# microwaveBoardAntenna.net
KiCad netlist of a schematic drawn in Altium Designer
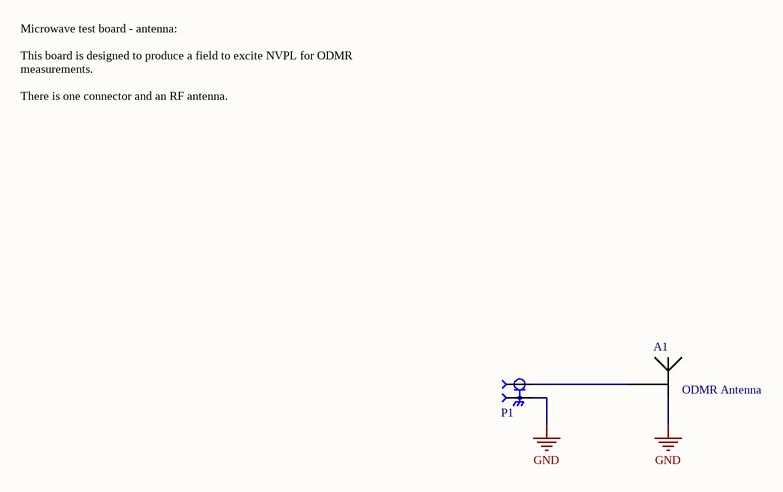
[diagram p0: microwaveBoardAntenna.SchDoc]

(export (version "E")
  (design (tool "Eeschema 10.0.6"))
  (components
    (comp (ref "A1")
      (value "ODMR Antenna")
      (footprint "ODMR_Antenna")
      (description "antenna")
      (libsource (lib "SorensenCustom") (part "Patch Antenna"))
    )
    (comp (ref "P1")
      (value "MMCXV-J-P-HF-ST-EM1")
      (footprint "MMCXV-J-P-HF-ST-EM1")
      (description "50 OHM MMCX HIGH-VIBRATION JACK,")
      (fields (field (name "PART NUMBER") "PXX-SAM-00013") (field (name "PUBLISHER") "AlbertaSat"))
      (libsource (lib "Database") (part "MMCXV-J-P-HF-ST-EM1"))
    )
  )
  (nets
    (net (code "1") (name "GND") (class "Default")
      (node (ref "A1") (pin "2") (pinfunction "in_2") (pintype "passive"))
      (node (ref "P1") (pin "2") (pinfunction "2_2") (pintype "passive"))
    )
    (net (code "2") (name "Net-(A1-Pad1)") (class "Default")
      (node (ref "A1") (pin "1") (pinfunction "1_1") (pintype "passive"))
      (node (ref "P1") (pin "1") (pinfunction "1_1") (pintype "passive"))
    )
  )
)
